# 150244-1-legoled-v1_1.net
KiCad netlist of a schematic drawn in EAGLE
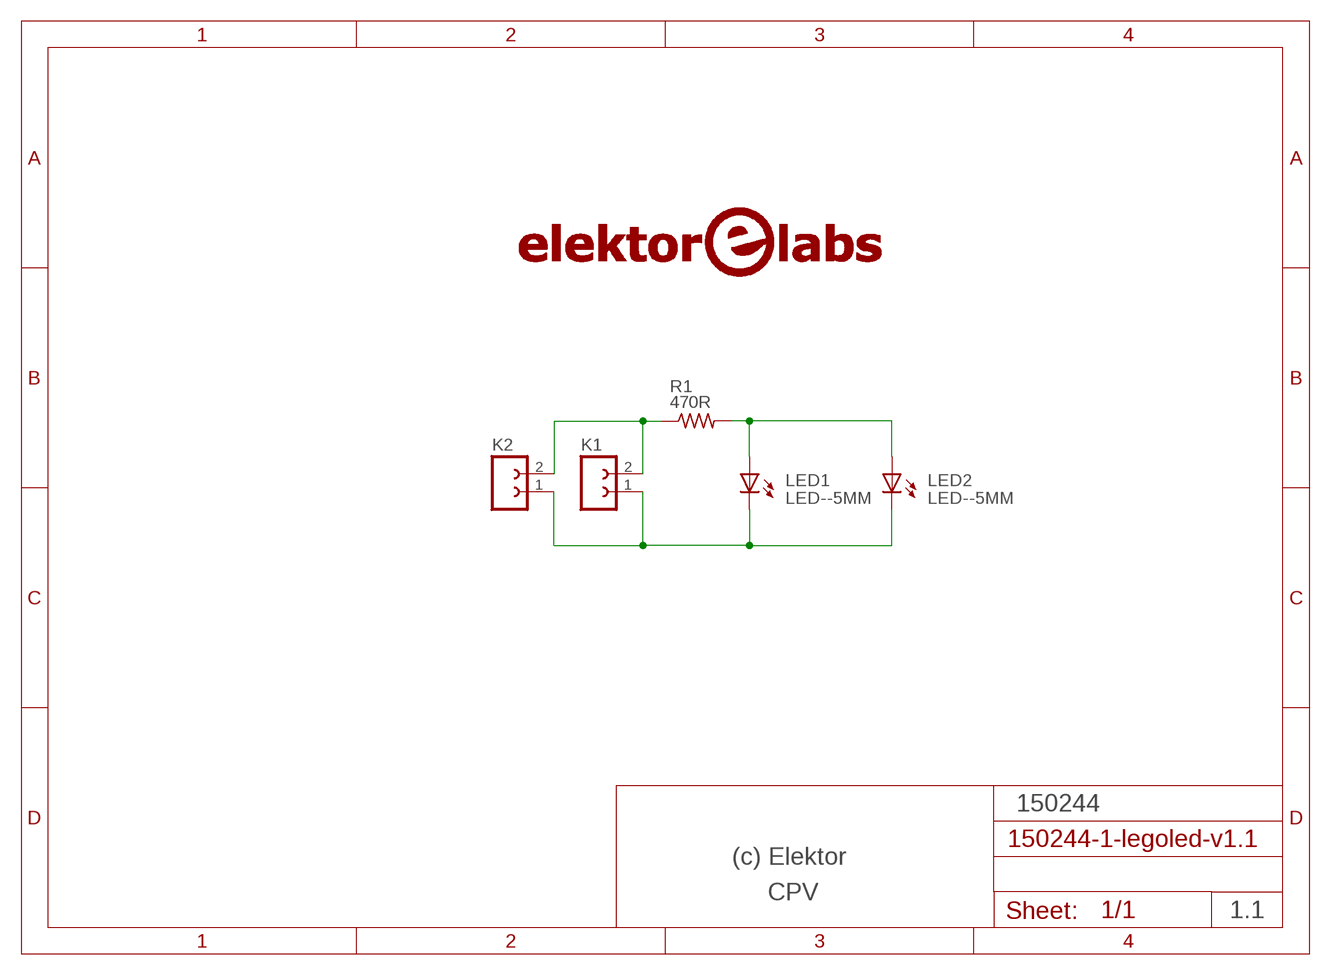
[diagram p0: schematic, sheet 1]

(export (version "E")
  (design (tool "Eeschema 10.0.6"))
  (components
    (comp (ref "K1")
      (value "K-HEADER-FEMALE-1X2-H")
      (footprint "eagle-import:EPP-SIL-F-2-WAY-90DEG")
      (libsource (lib "eagle-import") (part "K-HEADER-FEMALE-1X2-H"))
    )
    (comp (ref "K2")
      (value "K-HEADER-FEMALE-1X2-H")
      (footprint "eagle-import:EPP-SIL-F-2-WAY-90DEG")
      (libsource (lib "eagle-import") (part "K-HEADER-FEMALE-1X2-H"))
    )
    (comp (ref "LED1")
      (value "LED--5MM")
      (footprint "eagle-import:EPP-LED-5MM")
      (libsource (lib "eagle-import") (part "LED--5MM"))
    )
    (comp (ref "LED2")
      (value "LED--5MM")
      (footprint "eagle-import:EPP-LED-5MM")
      (libsource (lib "eagle-import") (part "LED--5MM"))
    )
    (comp (ref "LOGO1")
      (value "LOGO-ELEKTOR-LABS-18MM-V2")
      (footprint "eagle-import:EPP-LOGO-ELEKTOR-LABS-V2-18MM")
      (libsource (lib "eagle-import") (part "LOGO-ELEKTOR-LABS-18MM-V2"))
    )
    (comp (ref "R1")
      (value "470R")
      (footprint "eagle-import:R0805")
      (libsource (lib "eagle-import") (part "R-US_R0805"))
    )
  )
  (nets
    (net (code "1") (name "Net-(K1-Pad1)") (class "Default")
      (node (ref "K1") (pin "1") (pinfunction "1_1") (pintype "passive"))
      (node (ref "K2") (pin "1") (pinfunction "1_1") (pintype "passive"))
      (node (ref "LED1") (pin "C") (pinfunction "C_C") (pintype "passive"))
      (node (ref "LED2") (pin "C") (pinfunction "C_C") (pintype "passive"))
    )
    (net (code "2") (name "Net-(K1-Pad2)") (class "Default")
      (node (ref "K1") (pin "2") (pinfunction "2_2") (pintype "passive"))
      (node (ref "K2") (pin "2") (pinfunction "2_2") (pintype "passive"))
      (node (ref "R1") (pin "1") (pinfunction "1_1") (pintype "passive"))
    )
    (net (code "3") (name "Net-(LED1-PadA)") (class "Default")
      (node (ref "LED1") (pin "A") (pinfunction "A_A") (pintype "passive"))
      (node (ref "LED2") (pin "A") (pinfunction "A_A") (pintype "passive"))
      (node (ref "R1") (pin "2") (pinfunction "2_2") (pintype "passive"))
    )
  )
)
